# Main.net
KiCad netlist of a schematic drawn in Altium Designer
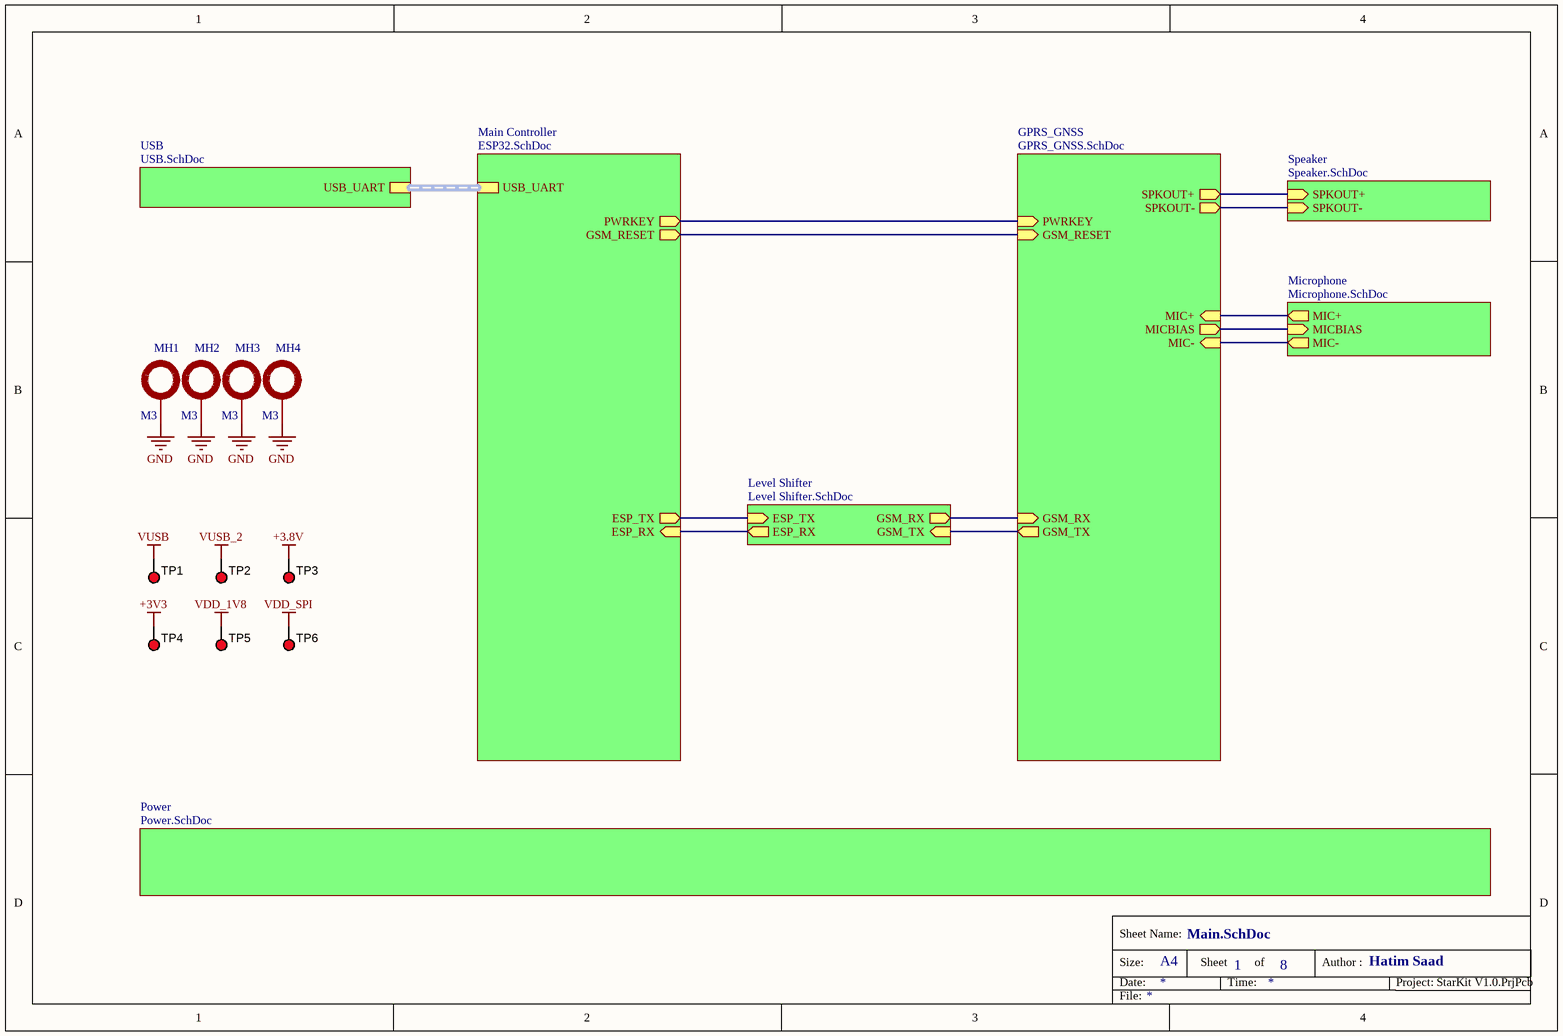
[diagram p0: Main.SchDoc]

(export (version "E")
  (design (tool "Eeschema 10.0.6"))
  (components
    (comp (ref "MH1")
      (value "M3")
      (footprint "M3 Mounting Hole")
      (description "Mounting Hole M3 Screw")
      (libsource (lib "HZSchLib") (part "Mounting Hole M3"))
    )
    (comp (ref "MH2")
      (value "M3")
      (footprint "M3 Mounting Hole")
      (description "Mounting Hole M3 Screw")
      (libsource (lib "HZSchLib") (part "Mounting Hole M3"))
    )
    (comp (ref "MH3")
      (value "M3")
      (footprint "M3 Mounting Hole")
      (description "Mounting Hole M3 Screw")
      (libsource (lib "HZSchLib") (part "Mounting Hole M3"))
    )
    (comp (ref "MH4")
      (value "M3")
      (footprint "M3 Mounting Hole")
      (description "Mounting Hole M3 Screw")
      (libsource (lib "HZSchLib") (part "Mounting Hole M3"))
    )
    (comp (ref "TP1")
      (value "5010")
      (footprint "test point")
      (description "Test Point, Multipurpose, Red, TH")
      (fields (field (name "MANUFACTURER") "Keystone") (field (name "PUBLISHER") "Texas Instruments"))
      (libsource (lib "HZSchLib") (part "test point"))
    )
    (comp (ref "TP2")
      (value "5010")
      (footprint "test point")
      (description "Test Point, Multipurpose, Red, TH")
      (fields (field (name "MANUFACTURER") "Keystone") (field (name "PUBLISHER") "Texas Instruments"))
      (libsource (lib "HZSchLib") (part "test point"))
    )
    (comp (ref "TP3")
      (value "5010")
      (footprint "test point")
      (description "Test Point, Multipurpose, Red, TH")
      (fields (field (name "MANUFACTURER") "Keystone") (field (name "PUBLISHER") "Texas Instruments"))
      (libsource (lib "HZSchLib") (part "test point"))
    )
    (comp (ref "TP4")
      (value "5010")
      (footprint "test point")
      (description "Test Point, Multipurpose, Red, TH")
      (fields (field (name "MANUFACTURER") "Keystone") (field (name "PUBLISHER") "Texas Instruments"))
      (libsource (lib "HZSchLib") (part "test point"))
    )
    (comp (ref "TP5")
      (value "5010")
      (footprint "test point")
      (description "Test Point, Multipurpose, Red, TH")
      (fields (field (name "MANUFACTURER") "Keystone") (field (name "PUBLISHER") "Texas Instruments"))
      (libsource (lib "HZSchLib") (part "test point"))
    )
    (comp (ref "TP6")
      (value "5010")
      (footprint "test point")
      (description "Test Point, Multipurpose, Red, TH")
      (fields (field (name "MANUFACTURER") "Keystone") (field (name "PUBLISHER") "Texas Instruments"))
      (libsource (lib "HZSchLib") (part "test point"))
    )
  )
  (nets
    (net (code "1") (name "+3.8V") (class "Default") (node (ref "TP3") (pin "1") (pintype "passive")))
    (net (code "2") (name "+3V3") (class "Default") (node (ref "TP4") (pin "1") (pintype "passive")))
    (net (code "15") (name "GND") (class "Default")
      (node (ref "MH1") (pin "1") (pinfunction "1_1") (pintype "passive"))
      (node (ref "MH2") (pin "1") (pinfunction "1_1") (pintype "passive"))
      (node (ref "MH3") (pin "1") (pinfunction "1_1") (pintype "passive"))
      (node (ref "MH4") (pin "1") (pinfunction "1_1") (pintype "passive"))
    )
    (net (code "16") (name "VDD_1V8") (class "Default") (node (ref "TP5") (pin "1") (pintype "passive")))
    (net (code "17") (name "VDD_SPI") (class "Default") (node (ref "TP6") (pin "1") (pintype "passive")))
    (net (code "18") (name "VUSB") (class "Default") (node (ref "TP1") (pin "1") (pintype "passive")))
    (net (code "19") (name "VUSB_2") (class "Default") (node (ref "TP2") (pin "1") (pintype "passive")))
  )
)
